# MIDI.net
KiCad netlist of a schematic drawn in Altium Designer
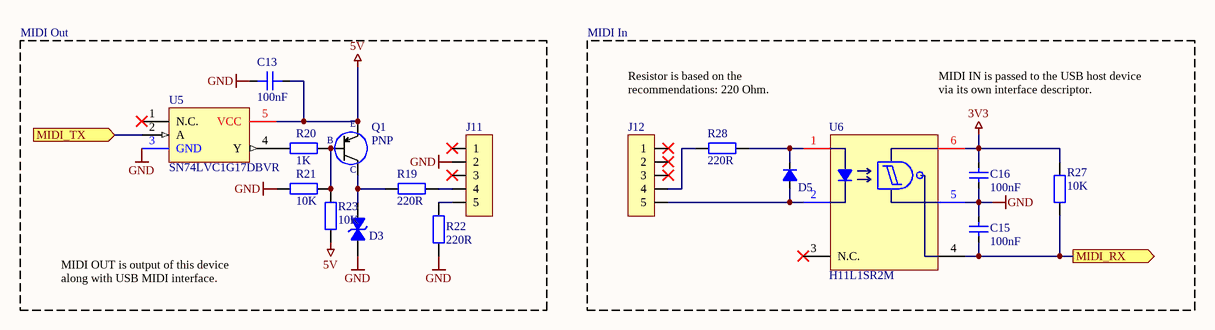
[diagram p0: MIDI.SchDoc]

(export (version "E")
  (design (tool "Eeschema 10.0.6"))
  (components
    (comp (ref "C13")
      (value "100nF")
      (footprint "0603C_RF_M")
      (description "Capacitor")
      (fields (field (name "TOLERANCE") "?") (field (name "MANUFACTURER") "Generic Brand"))
      (libsource (lib "AG.Generic") (part "C"))
    )
    (comp (ref "C15")
      (value "100nF")
      (footprint "0603C_RF_M")
      (description "Capacitor")
      (fields (field (name "TOLERANCE") "?") (field (name "MANUFACTURER") "Generic Brand"))
      (libsource (lib "") (part "C_1"))
    )
    (comp (ref "C16")
      (value "100nF")
      (footprint "0603C_RF_M")
      (description "Capacitor")
      (fields (field (name "TOLERANCE") "?") (field (name "MANUFACTURER") "Generic Brand"))
      (libsource (lib "") (part "C_1"))
    )
    (comp (ref "D3")
      (value "TVS")
      (footprint "NXP_SOD-323_RF_M")
      (description "TVS Diode Bidirectional")
      (fields (field (name "MANUFACTURER") "Generic Brand"))
      (libsource (lib "AG.Generic") (part "D-TVS"))
    )
    (comp (ref "D5")
      (value "D")
      (footprint "NXP_SOD-323_RF_M")
      (description "Diode (Rectifier)")
      (fields (field (name "MANUFACTURER") "Generic Brand"))
      (libsource (lib "AG.Generic") (part "D"))
    )
    (comp (ref "J11")
      (value "PINHDR-5P1")
      (footprint "AG.Connectors:HEADER-2.54-5P1")
      (description "Generic Pin Header 5x1")
      (libsource (lib "") (part "PINHDR-5P1_1"))
    )
    (comp (ref "J12")
      (value "PINHDR-5P1")
      (footprint "AG.Connectors:HEADER-2.54-5P1")
      (description "Generic Pin Header 5x1")
      (libsource (lib "AG.Connectors") (part "PINHDR-5P1"))
    )
    (comp (ref "Q1")
      (value "PNP")
      (footprint "SOT-23-3")
      (description "Bipolar Transistor PNP")
      (fields (field (name "MANUFACTURER") "Generic Brand"))
      (libsource (lib "AG.Generic") (part "PNP"))
    )
    (comp (ref "R19")
      (value "220R")
      (footprint "0603R_RF_M")
      (description "Resistor")
      (fields (field (name "TOLERANCE") "?") (field (name "MANUFACTURER") "Generic Brand"))
      (libsource (lib "AG.Generic") (part "R"))
    )
    (comp (ref "R20")
      (value "1K")
      (footprint "0603R_RF_M")
      (description "Resistor")
      (fields (field (name "TOLERANCE") "?") (field (name "MANUFACTURER") "Generic Brand"))
      (libsource (lib "AG.Generic") (part "R"))
    )
    (comp (ref "R21")
      (value "10K")
      (footprint "0603R_RF_M")
      (description "Resistor")
      (fields (field (name "TOLERANCE") "?") (field (name "MANUFACTURER") "Generic Brand"))
      (libsource (lib "AG.Generic") (part "R"))
    )
    (comp (ref "R22")
      (value "220R")
      (footprint "0603R_RF_M")
      (description "Resistor")
      (fields (field (name "TOLERANCE") "?") (field (name "MANUFACTURER") "Generic Brand"))
      (libsource (lib "AG.Generic") (part "R"))
    )
    (comp (ref "R23")
      (value "10K")
      (footprint "0603R_RF_M")
      (description "Resistor")
      (fields (field (name "TOLERANCE") "?") (field (name "MANUFACTURER") "Generic Brand"))
      (libsource (lib "AG.Generic") (part "R"))
    )
    (comp (ref "R27")
      (value "10K")
      (footprint "0603R_RF_M")
      (description "Resistor")
      (fields (field (name "TOLERANCE") "?") (field (name "MANUFACTURER") "Generic Brand"))
      (libsource (lib "AG.Generic") (part "R"))
    )
    (comp (ref "R28")
      (value "220R")
      (footprint "0603R_RF_M")
      (description "Resistor")
      (fields (field (name "TOLERANCE") "?") (field (name "MANUFACTURER") "Generic Brand"))
      (libsource (lib "AG.Generic") (part "R"))
    )
    (comp (ref "U5")
      (value "SN74LVC1G17DBVR")
      (footprint "TI_SOT-23-5")
      (description "IC BUF NON-INVERT 5.5V SOT23-5")
      (fields (field (name "MANUFACTURER") "Texas Instruments"))
      (libsource (lib "AG.IC") (part "SN74LVC1G17DBVR"))
    )
    (comp (ref "U6")
      (value "H11L1SR2M")
      (footprint "H11L1SR2M_SMD-6")
      (description "OPTOISO 4.17KV OPN COLL SMD-6")
      (fields
        (field (name "MANUFACTURER") "ON Semiconductor")
        (field (name "ALTERNATIVE SUPPLIER PART NO") "753715628")
      )
      (libsource (lib "AG.IC") (part "H11L1SR2M"))
    )
  )
  (nets
    (net (code "1") (name "/MIDI_RX") (class "Default")
      (node (ref "C15") (pin "1") (pinfunction "1_1") (pintype "passive"))
      (node (ref "R27") (pin "2") (pintype "passive"))
      (node (ref "U6") (pin "4") (pinfunction "OUT_4") (pintype "passive"))
    )
    (net (code "2") (name "/MIDI_TX") (class "Default")
      (node (ref "U5") (pin "2") (pinfunction "A_2") (pintype "input"))
    )
    (net (code "3") (name "3V3") (class "Default")
      (node (ref "C16") (pin "2") (pinfunction "2_2") (pintype "passive"))
      (node (ref "R27") (pin "1") (pintype "passive"))
      (node (ref "U6") (pin "6") (pinfunction "VCC_6") (pintype "power_in"))
    )
    (net (code "4") (name "5V") (class "Default")
      (node (ref "C13") (pin "2") (pinfunction "2_2") (pintype "passive"))
      (node (ref "Q1") (pin "E") (pinfunction "Emmiter_E") (pintype "passive"))
      (node (ref "R23") (pin "2") (pintype "passive"))
      (node (ref "U5") (pin "5") (pinfunction "VCC_5") (pintype "power_in"))
    )
    (net (code "5") (name "GND") (class "Default")
      (node (ref "C13") (pin "1") (pinfunction "1_1") (pintype "passive"))
      (node (ref "C15") (pin "2") (pinfunction "2_2") (pintype "passive"))
      (node (ref "C16") (pin "1") (pinfunction "1_1") (pintype "passive"))
      (node (ref "D3") (pin "A") (pinfunction "A_A") (pintype "passive"))
      (node (ref "J11") (pin "2") (pinfunction "2_2") (pintype "passive"))
      (node (ref "R21") (pin "2") (pintype "passive"))
      (node (ref "R22") (pin "1") (pintype "passive"))
      (node (ref "U5") (pin "3") (pinfunction "GND_3") (pintype "power_in"))
      (node (ref "U6") (pin "5") (pinfunction "GND_5") (pintype "power_in"))
    )
    (net (code "6") (name "Net-(J11-Pad4)") (class "Default")
      (node (ref "J11") (pin "4") (pinfunction "4_4") (pintype "passive"))
      (node (ref "R19") (pin "2") (pintype "passive"))
    )
    (net (code "7") (name "Net-(J11-Pad5)") (class "Default")
      (node (ref "J11") (pin "5") (pinfunction "5_5") (pintype "passive"))
      (node (ref "R22") (pin "2") (pintype "passive"))
    )
    (net (code "8") (name "Net-(J12-Pad4)") (class "Default")
      (node (ref "J12") (pin "4") (pinfunction "4_4") (pintype "passive"))
      (node (ref "R28") (pin "1") (pintype "passive"))
    )
    (net (code "9") (name "Net-(Q1-Base)") (class "Default")
      (node (ref "Q1") (pin "B") (pinfunction "Base_B") (pintype "passive"))
      (node (ref "R20") (pin "1") (pintype "passive"))
      (node (ref "R21") (pin "1") (pintype "passive"))
      (node (ref "R23") (pin "1") (pintype "passive"))
    )
    (net (code "10") (name "Net-(Q1-Collector)") (class "Default")
      (node (ref "D3") (pin "C") (pinfunction "C_C") (pintype "passive"))
      (node (ref "Q1") (pin "C") (pinfunction "Collector_C") (pintype "passive"))
      (node (ref "R19") (pin "1") (pintype "passive"))
    )
    (net (code "11") (name "Net-(U5-Y)") (class "Default")
      (node (ref "R20") (pin "2") (pintype "passive"))
      (node (ref "U5") (pin "4") (pinfunction "Y_4") (pintype "output"))
    )
    (net (code "12") (name "Net-(U6-A)") (class "Default")
      (node (ref "D5") (pin "C") (pinfunction "C_C") (pintype "passive"))
      (node (ref "R28") (pin "2") (pintype "passive"))
      (node (ref "U6") (pin "1") (pinfunction "A_1") (pintype "passive"))
    )
    (net (code "13") (name "Net-(U6-C)") (class "Default")
      (node (ref "D5") (pin "A") (pinfunction "A_A") (pintype "passive"))
      (node (ref "J12") (pin "5") (pinfunction "5_5") (pintype "passive"))
      (node (ref "U6") (pin "2") (pinfunction "C_2") (pintype "passive"))
    )
    (net (code "14") (name "unconnected-(J11-Pad1)") (class "Default")
      (node (ref "J11") (pin "1") (pinfunction "1_1") (pintype "passive+no_connect"))
    )
    (net (code "15") (name "unconnected-(J11-Pad3)") (class "Default")
      (node (ref "J11") (pin "3") (pinfunction "3_3") (pintype "passive+no_connect"))
    )
    (net (code "16") (name "unconnected-(J12-Pad1)") (class "Default")
      (node (ref "J12") (pin "1") (pinfunction "1_1") (pintype "passive+no_connect"))
    )
    (net (code "17") (name "unconnected-(J12-Pad2)") (class "Default")
      (node (ref "J12") (pin "2") (pinfunction "2_2") (pintype "passive+no_connect"))
    )
    (net (code "18") (name "unconnected-(J12-Pad3)") (class "Default")
      (node (ref "J12") (pin "3") (pinfunction "3_3") (pintype "passive+no_connect"))
    )
    (net (code "19") (name "unconnected-(U5-N.C.-Pad1)") (class "Default")
      (node (ref "U5") (pin "1") (pinfunction "N.C._1") (pintype "passive+no_connect"))
    )
    (net (code "20") (name "unconnected-(U6-N.C.-Pad3)") (class "Default")
      (node (ref "U6") (pin "3") (pinfunction "N.C._3") (pintype "passive+no_connect"))
    )
  )
)
